# led_driver.net
KiCad netlist of a schematic drawn in EAGLE
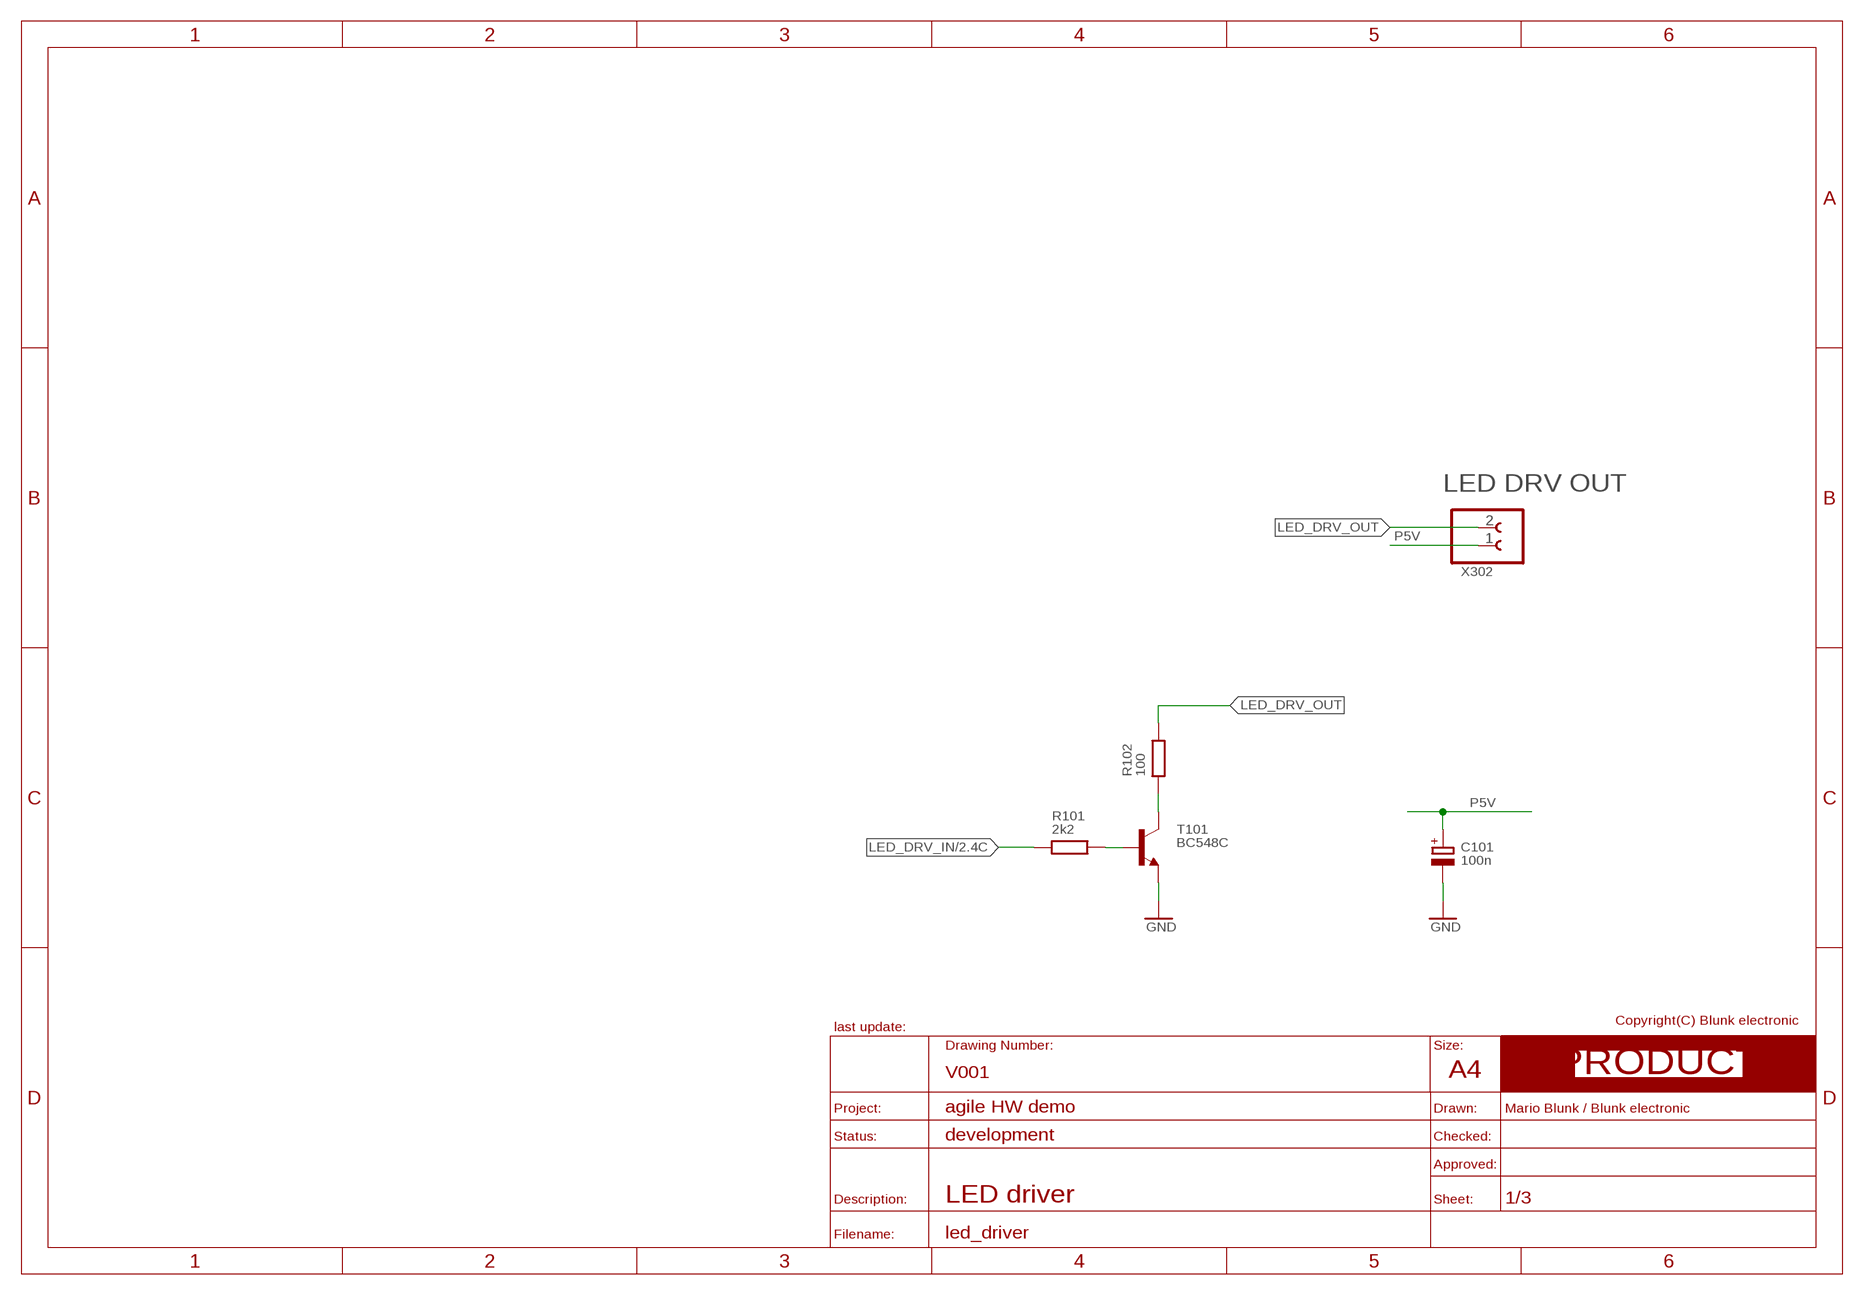
[diagram p0: schematic, sheet 1]
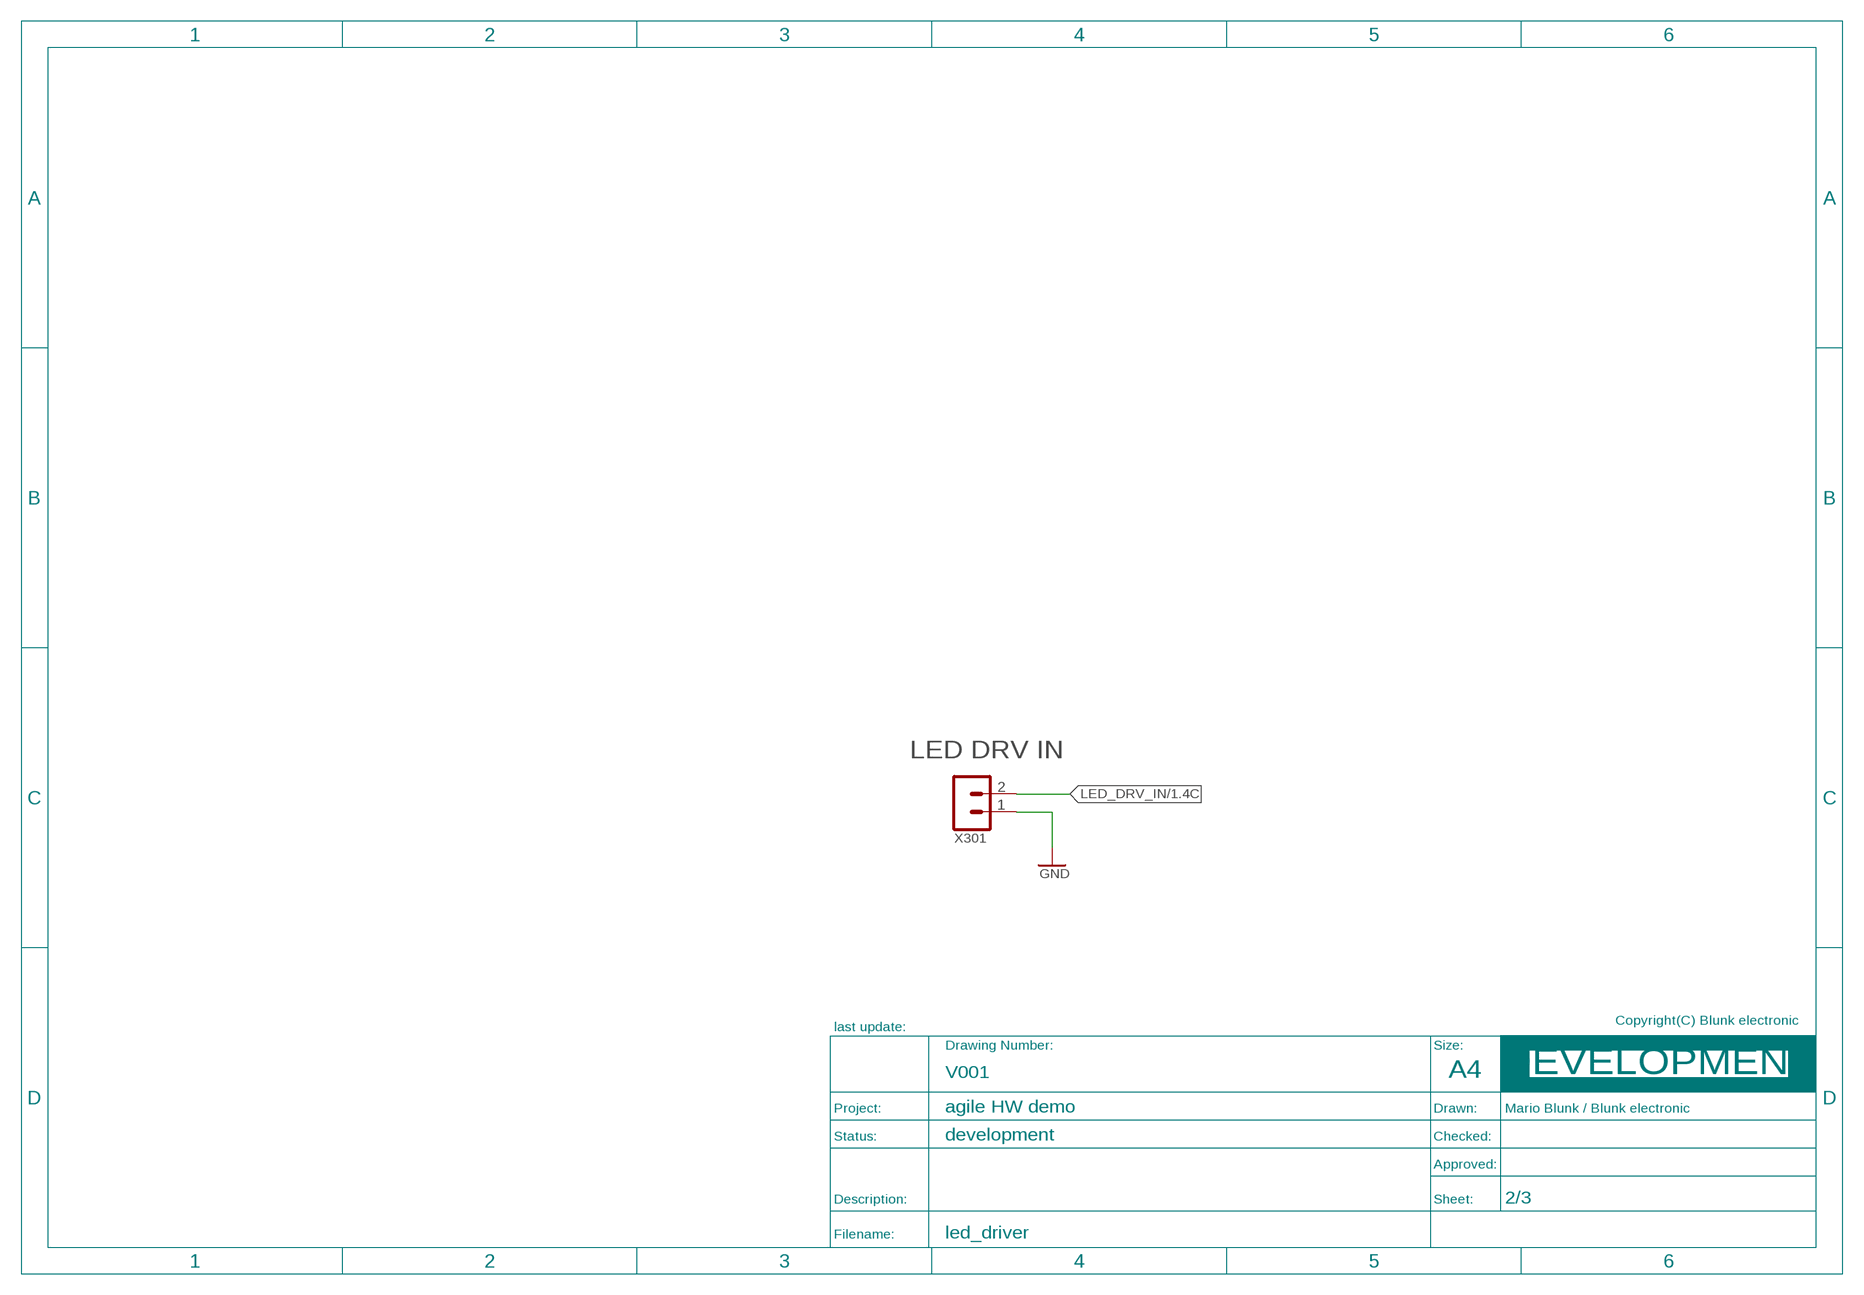
[diagram p1: schematic, sheet 2]
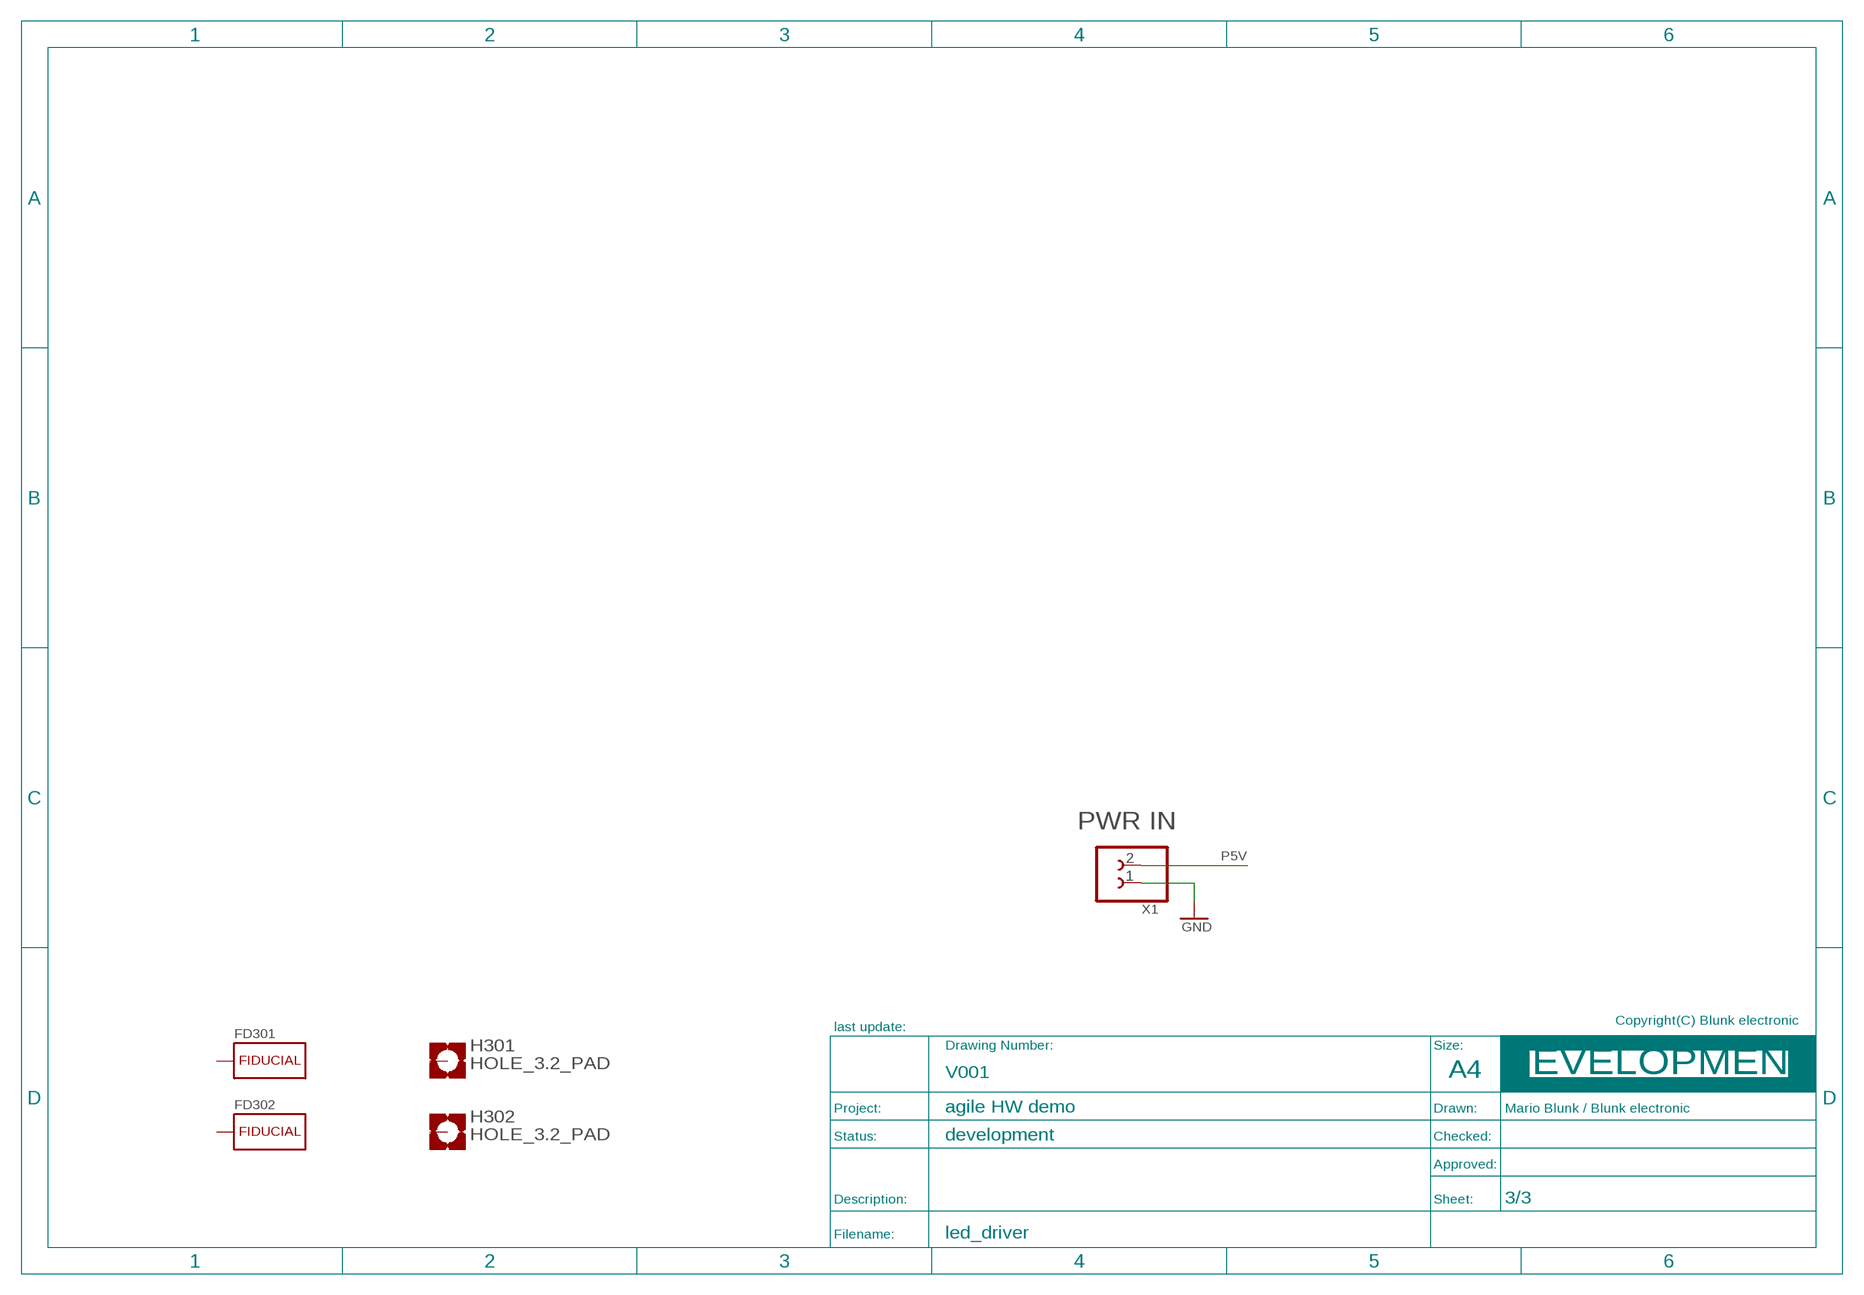
[diagram p2: schematic, sheet 3]

(export (version "E")
  (design (tool "Eeschema 10.0.6"))
  (components
    (comp (ref "C101")
      (value "100n")
      (footprint "eagle-import:S_6032")
      (libsource (lib "eagle-import") (part "C_POL_S_6032"))
    )
    (comp (ref "R101")
      (value "2k2")
      (footprint "eagle-import:S_0805")
      (libsource (lib "eagle-import") (part "R_S_0805"))
    )
    (comp (ref "R102")
      (value "100")
      (footprint "eagle-import:S_0805")
      (libsource (lib "eagle-import") (part "R_S_0805"))
    )
    (comp (ref "T101")
      (value "BC548C")
      (footprint "eagle-import:S_SOT23")
      (libsource (lib "eagle-import") (part "NPN_S_SOT23"))
    )
    (comp (ref "X302")
      (value "CLAMP_1X2-T-2.5MM")
      (footprint "eagle-import:T_WIRE_CLAMP_1X2_PITCH_2MM5")
      (fields (field (name "FUNCTION") "LED DRV OUT"))
      (libsource (lib "eagle-import") (part "CLAMP_1X2-T-2.5MM"))
    )
    (comp (ref "FD301")
      (value "FIDUCIAL_CROSSHAIR")
      (footprint "eagle-import:CROSSHAIR")
      (libsource (lib "eagle-import") (part "FIDUCIAL_CROSSHAIR"))
    )
    (comp (ref "FD302")
      (value "FIDUCIAL_CROSSHAIR")
      (footprint "eagle-import:CROSSHAIR")
      (libsource (lib "eagle-import") (part "FIDUCIAL_CROSSHAIR"))
    )
    (comp (ref "H301")
      (value "HOLE_3.2_PAD")
      (footprint "eagle-import:3.2_PAD")
      (libsource (lib "eagle-import") (part "HOLE_3.2_PAD"))
    )
    (comp (ref "H302")
      (value "HOLE_3.2_PAD")
      (footprint "eagle-import:3.2_PAD")
      (libsource (lib "eagle-import") (part "HOLE_3.2_PAD"))
    )
    (comp (ref "X1")
      (value "CLAMP_1X2-T-2.5MM")
      (footprint "eagle-import:T_WIRE_CLAMP_1X2_PITCH_2MM5")
      (fields (field (name "FUNCTION") "PWR IN"))
      (libsource (lib "eagle-import") (part "CLAMP_1X2-T-2.5MM"))
    )
    (comp (ref "X301")
      (value "MALE_2X1-T-VERTICAL")
      (footprint "eagle-import:T_MALE_2X1_VERTICAL_PITCH_2MM54")
      (fields (field (name "FUNCTION") "LED DRV IN"))
      (libsource (lib "eagle-import") (part "MALE_2X1-T-VERTICAL"))
    )
  )
  (nets
    (net (code "1") (name "GND") (class "Default")
      (node (ref "C101") (pin "-") (pinfunction "-_-") (pintype "passive"))
      (node (ref "T101") (pin "2") (pinfunction "E_2") (pintype "passive"))
      (node (ref "X1") (pin "1") (pinfunction "1_1") (pintype "passive"))
      (node (ref "X301") (pin "1") (pinfunction "1_1") (pintype "passive"))
    )
    (net (code "2") (name "LED_DRV_IN") (class "Default")
      (node (ref "R101") (pin "1") (pinfunction "1_1") (pintype "passive"))
      (node (ref "X301") (pin "2") (pinfunction "2_2") (pintype "passive"))
    )
    (net (code "3") (name "LED_DRV_OUT") (class "Default")
      (node (ref "R102") (pin "2") (pinfunction "2_2") (pintype "passive"))
      (node (ref "X302") (pin "2") (pinfunction "2_2") (pintype "passive"))
    )
    (net (code "4") (name "Net-(T101-B)") (class "Default")
      (node (ref "R101") (pin "2") (pinfunction "2_2") (pintype "passive"))
      (node (ref "T101") (pin "1") (pinfunction "B_1") (pintype "passive"))
    )
    (net (code "5") (name "Net-(T101-C)") (class "Default")
      (node (ref "R102") (pin "1") (pinfunction "1_1") (pintype "passive"))
      (node (ref "T101") (pin "3") (pinfunction "C_3") (pintype "passive"))
    )
    (net (code "6") (name "P5V") (class "Default")
      (node (ref "C101") (pin "+") (pinfunction "+_+") (pintype "passive"))
      (node (ref "X1") (pin "2") (pinfunction "2_2") (pintype "passive"))
      (node (ref "X302") (pin "1") (pinfunction "1_1") (pintype "passive"))
    )
    (net (code "7") (name "unconnected-(FD301-NC-Pad1)") (class "Default")
      (node (ref "FD301") (pin "1") (pinfunction "NC_1") (pintype "no_connect"))
    )
    (net (code "8") (name "unconnected-(FD302-NC-Pad1)") (class "Default")
      (node (ref "FD302") (pin "1") (pinfunction "NC_1") (pintype "no_connect"))
    )
    (net (code "9") (name "unconnected-(H301-MOUNT-PadH1)") (class "Default")
      (node (ref "H301") (pin "H1") (pinfunction "MOUNT_H1") (pintype "passive"))
    )
    (net (code "10") (name "unconnected-(H302-MOUNT-PadH1)") (class "Default")
      (node (ref "H302") (pin "H1") (pinfunction "MOUNT_H1") (pintype "passive"))
    )
  )
)
